# mainboard.net
KiCad netlist of a schematic drawn in EAGLE
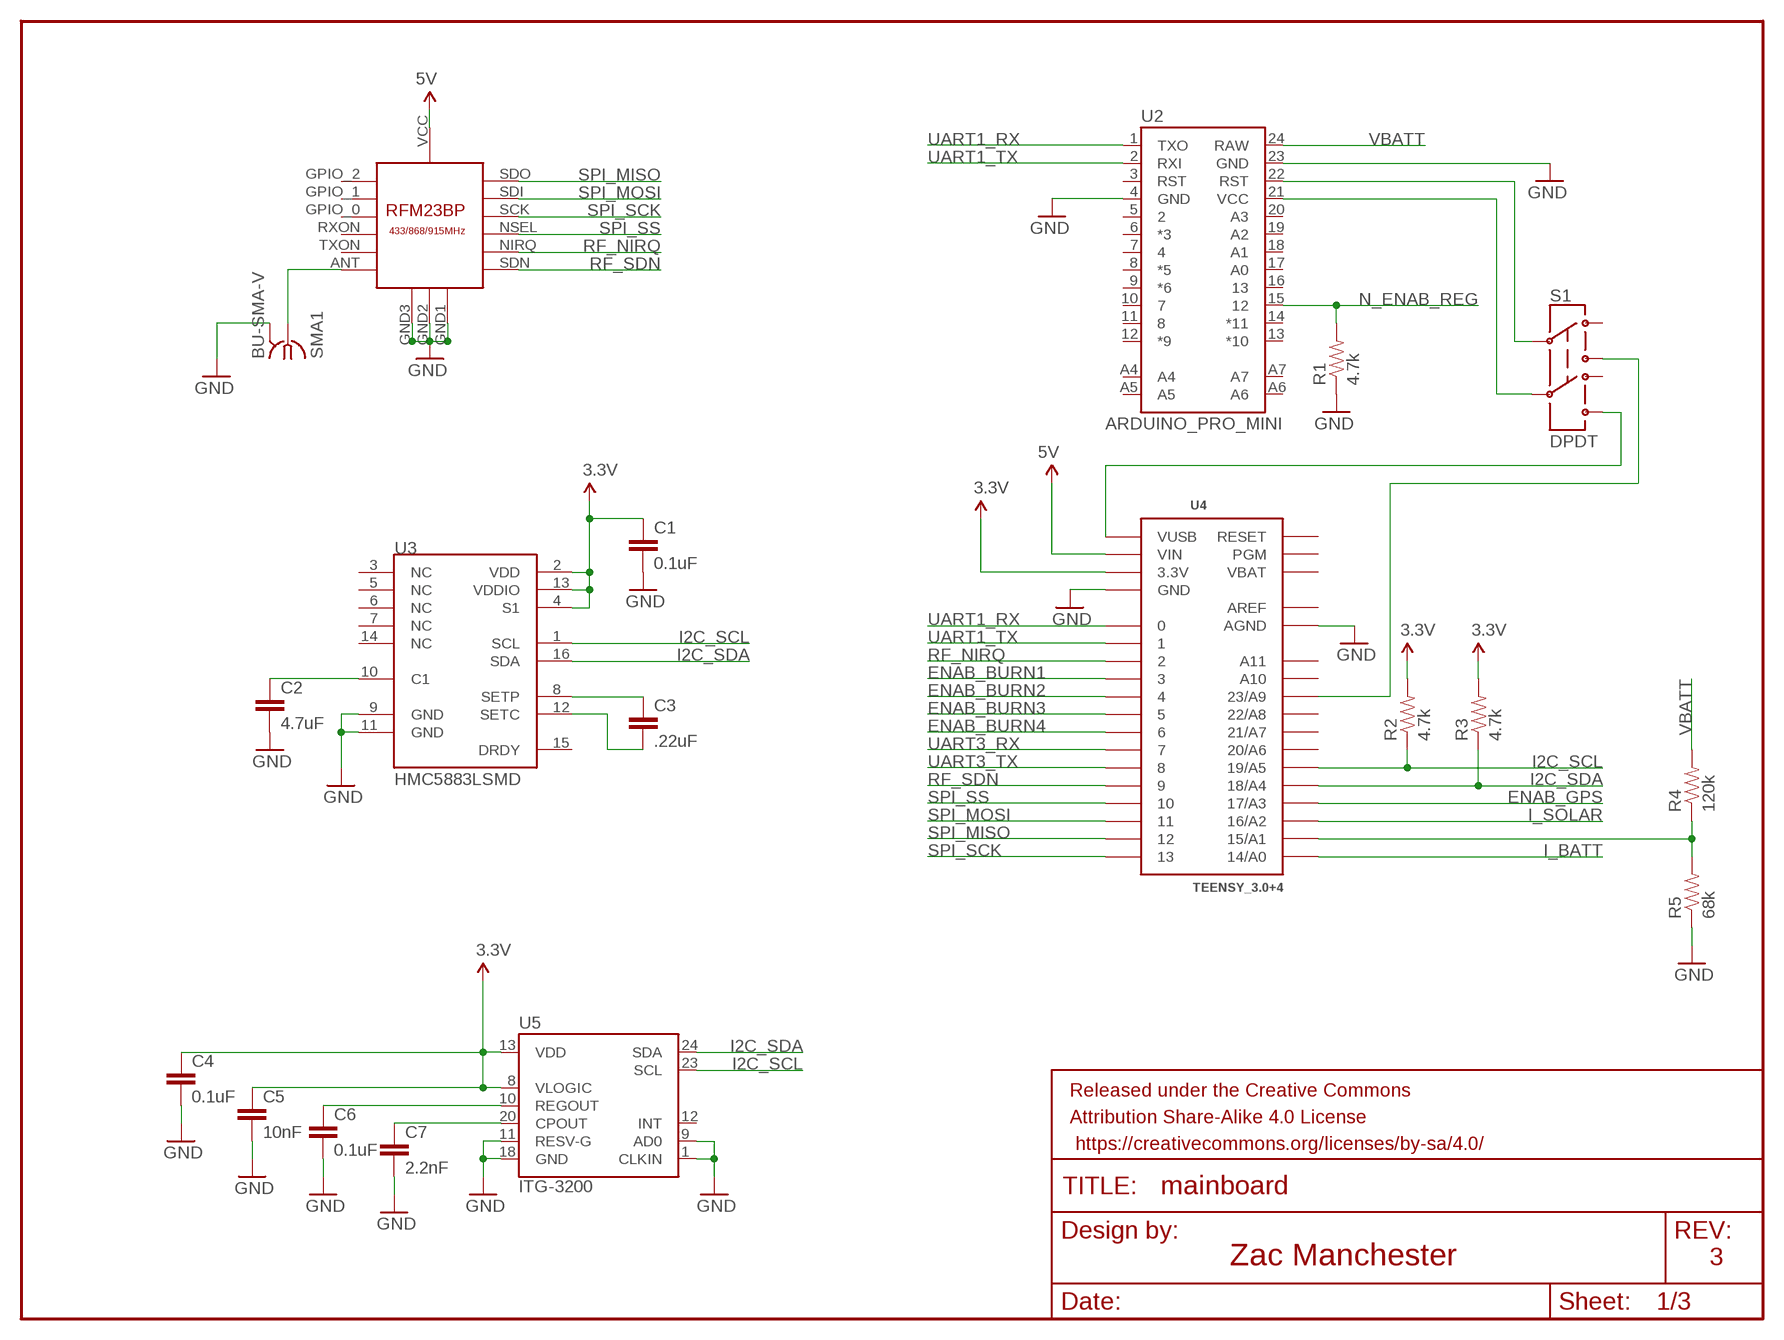
[diagram p0: schematic, sheet 1]
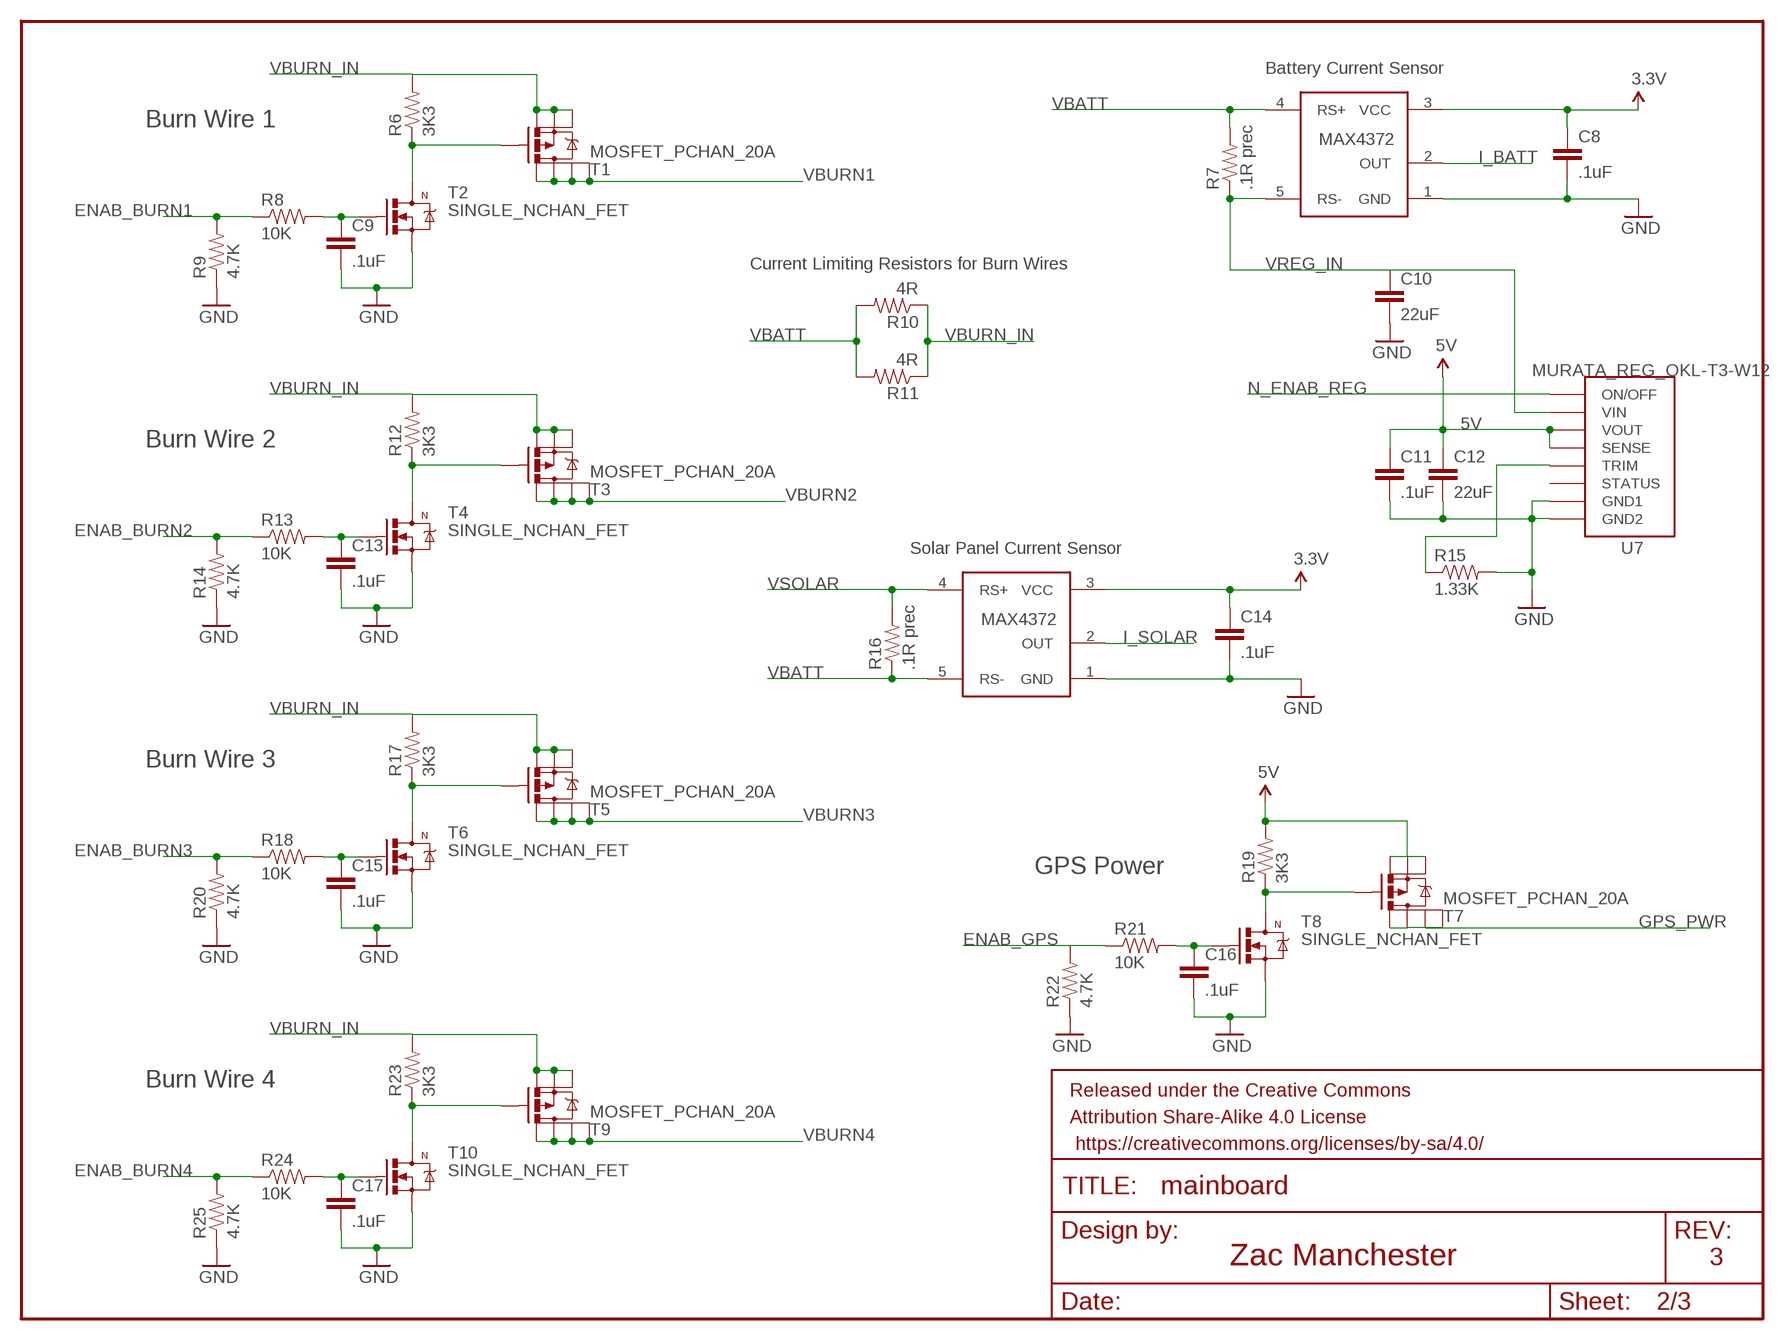
[diagram p1: schematic, sheet 2]
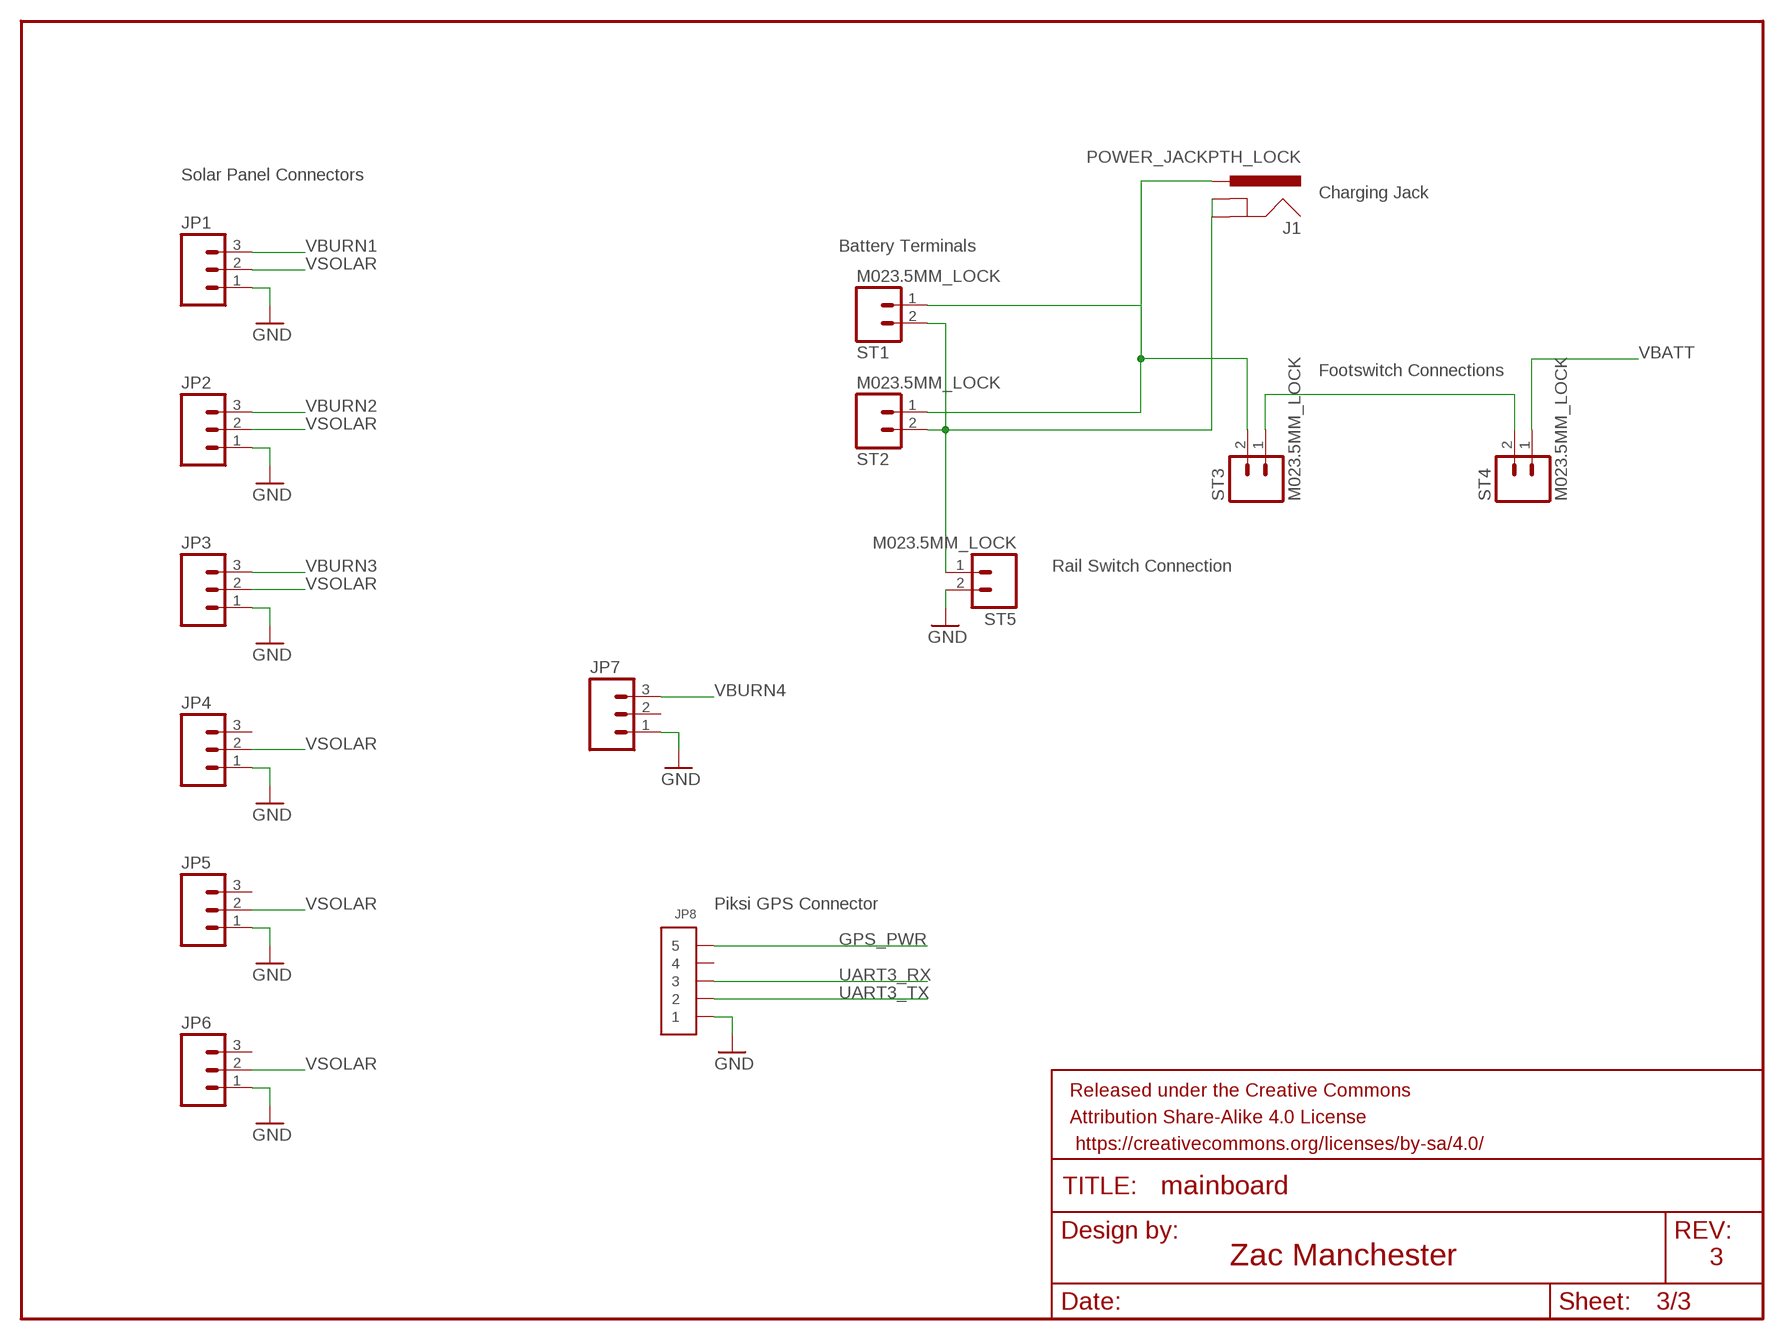
[diagram p2: schematic, sheet 3]

(export (version "E")
  (design (tool "Eeschema 10.0.6"))
  (components
    (comp (ref "FRAME3")
      (value "FRAME-LETTER")
      (footprint "eagle-import:CREATIVE_COMMONS")
      (libsource (lib "eagle-import") (part "FRAME-LETTER"))
    )
    (comp (ref "J1")
      (value "POWER_JACKPTH_LOCK")
      (footprint "eagle-import:POWER_JACK_PTH_LOCK")
      (libsource (lib "eagle-import") (part "POWER_JACKPTH_LOCK"))
    )
    (comp (ref "JP1")
      (value "M03POLAR_LOCK")
      (footprint "eagle-import:MOLEX-1X3_LOCK")
      (libsource (lib "eagle-import") (part "M03POLAR_LOCK"))
    )
    (comp (ref "JP2")
      (value "M03POLAR_LOCK")
      (footprint "eagle-import:MOLEX-1X3_LOCK")
      (libsource (lib "eagle-import") (part "M03POLAR_LOCK"))
    )
    (comp (ref "JP3")
      (value "M03POLAR_LOCK")
      (footprint "eagle-import:MOLEX-1X3_LOCK")
      (libsource (lib "eagle-import") (part "M03POLAR_LOCK"))
    )
    (comp (ref "JP4")
      (value "M03POLAR_LOCK")
      (footprint "eagle-import:MOLEX-1X3_LOCK")
      (libsource (lib "eagle-import") (part "M03POLAR_LOCK"))
    )
    (comp (ref "JP5")
      (value "M03POLAR_LOCK")
      (footprint "eagle-import:MOLEX-1X3_LOCK")
      (libsource (lib "eagle-import") (part "M03POLAR_LOCK"))
    )
    (comp (ref "JP6")
      (value "M03POLAR_LOCK")
      (footprint "eagle-import:MOLEX-1X3_LOCK")
      (libsource (lib "eagle-import") (part "M03POLAR_LOCK"))
    )
    (comp (ref "JP7")
      (value "M03POLAR_LOCK")
      (footprint "eagle-import:MOLEX-1X3_LOCK")
      (libsource (lib "eagle-import") (part "M03POLAR_LOCK"))
    )
    (comp (ref "JP8")
      (value "CONN_5-1-53261")
      (footprint "eagle-import:PB-53261-05")
      (libsource (lib "eagle-import") (part "CONN_5-1-53261"))
    )
    (comp (ref "ST1")
      (value "M023.5MM_LOCK")
      (footprint "eagle-import:SCREWTERMINAL-3.5MM-2_LOCK")
      (libsource (lib "eagle-import") (part "M023.5MM_LOCK"))
    )
    (comp (ref "ST2")
      (value "M023.5MM_LOCK")
      (footprint "eagle-import:SCREWTERMINAL-3.5MM-2_LOCK")
      (libsource (lib "eagle-import") (part "M023.5MM_LOCK"))
    )
    (comp (ref "ST3")
      (value "M023.5MM_LOCK")
      (footprint "eagle-import:SCREWTERMINAL-3.5MM-2_LOCK")
      (libsource (lib "eagle-import") (part "M023.5MM_LOCK"))
    )
    (comp (ref "ST4")
      (value "M023.5MM_LOCK")
      (footprint "eagle-import:SCREWTERMINAL-3.5MM-2_LOCK")
      (libsource (lib "eagle-import") (part "M023.5MM_LOCK"))
    )
    (comp (ref "ST5")
      (value "M023.5MM_LOCK")
      (footprint "eagle-import:SCREWTERMINAL-3.5MM-2_LOCK")
      (libsource (lib "eagle-import") (part "M023.5MM_LOCK"))
    )
    (comp (ref "C1")
      (value "0.1uF")
      (footprint "eagle-import:0805")
      (libsource (lib "eagle-import") (part "CAP0805"))
    )
    (comp (ref "C2")
      (value "4.7uF")
      (footprint "eagle-import:0805")
      (libsource (lib "eagle-import") (part "CAP0805"))
    )
    (comp (ref "C3")
      (value ".22uF")
      (footprint "eagle-import:0805")
      (libsource (lib "eagle-import") (part "CAP0805"))
    )
    (comp (ref "C4")
      (value "0.1uF")
      (footprint "eagle-import:0805")
      (libsource (lib "eagle-import") (part "CAP0805"))
    )
    (comp (ref "C5")
      (value "10nF")
      (footprint "eagle-import:0805")
      (libsource (lib "eagle-import") (part "CAP0805"))
    )
    (comp (ref "C6")
      (value "0.1uF")
      (footprint "eagle-import:0805")
      (libsource (lib "eagle-import") (part "CAP0805"))
    )
    (comp (ref "C7")
      (value "2.2nF")
      (footprint "eagle-import:0805")
      (libsource (lib "eagle-import") (part "CAP0805"))
    )
    (comp (ref "FRAME1")
      (value "FRAME-LETTER")
      (footprint "eagle-import:CREATIVE_COMMONS")
      (libsource (lib "eagle-import") (part "FRAME-LETTER"))
    )
    (comp (ref "R1")
      (value "4.7k")
      (footprint "eagle-import:0805")
      (libsource (lib "eagle-import") (part "RESISTOR0805-RES"))
    )
    (comp (ref "R2")
      (value "4.7k")
      (footprint "eagle-import:0805")
      (libsource (lib "eagle-import") (part "RESISTOR0805-RES"))
    )
    (comp (ref "R3")
      (value "4.7k")
      (footprint "eagle-import:0805")
      (libsource (lib "eagle-import") (part "RESISTOR0805-RES"))
    )
    (comp (ref "R4")
      (value "120k")
      (footprint "eagle-import:0805")
      (libsource (lib "eagle-import") (part "RESISTOR0805-RES"))
    )
    (comp (ref "R5")
      (value "68k")
      (footprint "eagle-import:0805")
      (libsource (lib "eagle-import") (part "RESISTOR0805-RES"))
    )
    (comp (ref "S1")
      (value "DPDT")
      (footprint "eagle-import:AYZ0202")
      (libsource (lib "eagle-import") (part "SWITCH-DPDTAYZ0202"))
    )
    (comp (ref "SMA1")
      (value "BU-SMA-V")
      (footprint "eagle-import:BU-SMA-V")
      (libsource (lib "eagle-import") (part "BU-SMA-V"))
    )
    (comp (ref "U1")
      (value "RFM23BP")
      (footprint "eagle-import:RFM23BP")
      (libsource (lib "eagle-import") (part "RFM23BP"))
    )
    (comp (ref "U2")
      (value "ARDUINO_PRO_MINI")
      (footprint "eagle-import:ARDUINO_PRO_MINI")
      (libsource (lib "eagle-import") (part "ARDUINO_PRO_MINI"))
    )
    (comp (ref "U3")
      (value "HMC5883LSMD")
      (footprint "eagle-import:16LPCC")
      (libsource (lib "eagle-import") (part "HMC5883LSMD"))
    )
    (comp (ref "U4")
      (value "TEENSY_3.0+4")
      (footprint "eagle-import:TEENSY_3.0+4")
      (libsource (lib "eagle-import") (part "TEENSY_3.0+4"))
    )
    (comp (ref "U5")
      (value "ITG-3200")
      (footprint "eagle-import:QFN-24")
      (libsource (lib "eagle-import") (part "ITG-3200"))
    )
    (comp (ref "C8")
      (value ".1uF")
      (footprint "eagle-import:0805")
      (libsource (lib "eagle-import") (part "CAP0805"))
    )
    (comp (ref "C9")
      (value ".1uF")
      (footprint "eagle-import:0805")
      (libsource (lib "eagle-import") (part "CAP0805"))
    )
    (comp (ref "C10")
      (value "22uF")
      (footprint "eagle-import:1206")
      (libsource (lib "eagle-import") (part "CAP1206"))
    )
    (comp (ref "C11")
      (value ".1uF")
      (footprint "eagle-import:0805")
      (libsource (lib "eagle-import") (part "CAP0805"))
    )
    (comp (ref "C12")
      (value "22uF")
      (footprint "eagle-import:1206")
      (libsource (lib "eagle-import") (part "CAP1206"))
    )
    (comp (ref "C13")
      (value ".1uF")
      (footprint "eagle-import:0805")
      (libsource (lib "eagle-import") (part "CAP0805"))
    )
    (comp (ref "C14")
      (value ".1uF")
      (footprint "eagle-import:0805")
      (libsource (lib "eagle-import") (part "CAP0805"))
    )
    (comp (ref "C15")
      (value ".1uF")
      (footprint "eagle-import:0805")
      (libsource (lib "eagle-import") (part "CAP0805"))
    )
    (comp (ref "C16")
      (value ".1uF")
      (footprint "eagle-import:0805")
      (libsource (lib "eagle-import") (part "CAP0805"))
    )
    (comp (ref "C17")
      (value ".1uF")
      (footprint "eagle-import:0805")
      (libsource (lib "eagle-import") (part "CAP0805"))
    )
    (comp (ref "FRAME2")
      (value "FRAME-LETTER")
      (footprint "eagle-import:CREATIVE_COMMONS")
      (libsource (lib "eagle-import") (part "FRAME-LETTER"))
    )
    (comp (ref "R6")
      (value "3K3")
      (footprint "eagle-import:0805")
      (libsource (lib "eagle-import") (part "RESISTOR0805-RES"))
    )
    (comp (ref "R7")
      (value ".1R prec")
      (footprint "eagle-import:0805")
      (libsource (lib "eagle-import") (part "RESISTOR0805-RES"))
    )
    (comp (ref "R8")
      (value "10K")
      (footprint "eagle-import:0805")
      (libsource (lib "eagle-import") (part "RESISTOR0805-RES"))
    )
    (comp (ref "R9")
      (value "4.7K")
      (footprint "eagle-import:0805")
      (libsource (lib "eagle-import") (part "RESISTOR0805-RES"))
    )
    (comp (ref "R10")
      (value "4R")
      (footprint "eagle-import:R2512")
      (libsource (lib "eagle-import") (part "RESISTOR2512"))
    )
    (comp (ref "R11")
      (value "4R")
      (footprint "eagle-import:R2512")
      (libsource (lib "eagle-import") (part "RESISTOR2512"))
    )
    (comp (ref "R12")
      (value "3K3")
      (footprint "eagle-import:0805")
      (libsource (lib "eagle-import") (part "RESISTOR0805-RES"))
    )
    (comp (ref "R13")
      (value "10K")
      (footprint "eagle-import:0805")
      (libsource (lib "eagle-import") (part "RESISTOR0805-RES"))
    )
    (comp (ref "R14")
      (value "4.7K")
      (footprint "eagle-import:0805")
      (libsource (lib "eagle-import") (part "RESISTOR0805-RES"))
    )
    (comp (ref "R15")
      (value "1.33K")
      (footprint "eagle-import:0805")
      (libsource (lib "eagle-import") (part "RESISTOR0805-RES"))
    )
    (comp (ref "R16")
      (value ".1R prec")
      (footprint "eagle-import:0805")
      (libsource (lib "eagle-import") (part "RESISTOR0805-RES"))
    )
    (comp (ref "R17")
      (value "3K3")
      (footprint "eagle-import:0805")
      (libsource (lib "eagle-import") (part "RESISTOR0805-RES"))
    )
    (comp (ref "R18")
      (value "10K")
      (footprint "eagle-import:0805")
      (libsource (lib "eagle-import") (part "RESISTOR0805-RES"))
    )
    (comp (ref "R19")
      (value "3K3")
      (footprint "eagle-import:0805")
      (libsource (lib "eagle-import") (part "RESISTOR0805-RES"))
    )
    (comp (ref "R20")
      (value "4.7K")
      (footprint "eagle-import:0805")
      (libsource (lib "eagle-import") (part "RESISTOR0805-RES"))
    )
    (comp (ref "R21")
      (value "10K")
      (footprint "eagle-import:0805")
      (libsource (lib "eagle-import") (part "RESISTOR0805-RES"))
    )
    (comp (ref "R22")
      (value "4.7K")
      (footprint "eagle-import:0805")
      (libsource (lib "eagle-import") (part "RESISTOR0805-RES"))
    )
    (comp (ref "R23")
      (value "3K3")
      (footprint "eagle-import:0805")
      (libsource (lib "eagle-import") (part "RESISTOR0805-RES"))
    )
    (comp (ref "R24")
      (value "10K")
      (footprint "eagle-import:0805")
      (libsource (lib "eagle-import") (part "RESISTOR0805-RES"))
    )
    (comp (ref "R25")
      (value "4.7K")
      (footprint "eagle-import:0805")
      (libsource (lib "eagle-import") (part "RESISTOR0805-RES"))
    )
    (comp (ref "T1")
      (value "MOSFET_PCHAN_20A")
      (footprint "eagle-import:SO8")
      (libsource (lib "eagle-import") (part "MOSFET_PCHAN_20A"))
    )
    (comp (ref "T2")
      (value "SINGLE_NCHAN_FET")
      (footprint "eagle-import:SOT23-3")
      (libsource (lib "eagle-import") (part "SINGLE_NCHAN_FET"))
    )
    (comp (ref "T3")
      (value "MOSFET_PCHAN_20A")
      (footprint "eagle-import:SO8")
      (libsource (lib "eagle-import") (part "MOSFET_PCHAN_20A"))
    )
    (comp (ref "T4")
      (value "SINGLE_NCHAN_FET")
      (footprint "eagle-import:SOT23-3")
      (libsource (lib "eagle-import") (part "SINGLE_NCHAN_FET"))
    )
    (comp (ref "T5")
      (value "MOSFET_PCHAN_20A")
      (footprint "eagle-import:SO8")
      (libsource (lib "eagle-import") (part "MOSFET_PCHAN_20A"))
    )
    (comp (ref "T6")
      (value "SINGLE_NCHAN_FET")
      (footprint "eagle-import:SOT23-3")
      (libsource (lib "eagle-import") (part "SINGLE_NCHAN_FET"))
    )
    (comp (ref "T7")
      (value "MOSFET_PCHAN_20A")
      (footprint "eagle-import:SO8")
      (libsource (lib "eagle-import") (part "MOSFET_PCHAN_20A"))
    )
    (comp (ref "T8")
      (value "SINGLE_NCHAN_FET")
      (footprint "eagle-import:SOT23-3")
      (libsource (lib "eagle-import") (part "SINGLE_NCHAN_FET"))
    )
    (comp (ref "T9")
      (value "MOSFET_PCHAN_20A")
      (footprint "eagle-import:SO8")
      (libsource (lib "eagle-import") (part "MOSFET_PCHAN_20A"))
    )
    (comp (ref "T10")
      (value "SINGLE_NCHAN_FET")
      (footprint "eagle-import:SOT23-3")
      (libsource (lib "eagle-import") (part "SINGLE_NCHAN_FET"))
    )
    (comp (ref "U6")
      (value "CURRENT_MAX4372")
      (footprint "eagle-import:SOT23-5")
      (libsource (lib "eagle-import") (part "CURRENT_MAX4372"))
    )
    (comp (ref "U7")
      (value "MURATA_REG_OKL-T3-W12")
      (footprint "eagle-import:MURATA_REG_OKL-T6-W12")
      (libsource (lib "eagle-import") (part "MURATA_REG_OKL-T6-W12"))
    )
    (comp (ref "U8")
      (value "CURRENT_MAX4372")
      (footprint "eagle-import:SOT23-5")
      (libsource (lib "eagle-import") (part "CURRENT_MAX4372"))
    )
  )
  (nets
    (net (code "1") (name "3.3V") (class "Default")
      (node (ref "C1") (pin "1") (pinfunction "1_1") (pintype "passive"))
      (node (ref "C14") (pin "1") (pinfunction "1_1") (pintype "passive"))
      (node (ref "C4") (pin "1") (pinfunction "1_1") (pintype "passive"))
      (node (ref "C5") (pin "1") (pinfunction "1_1") (pintype "passive"))
      (node (ref "C8") (pin "1") (pinfunction "1_1") (pintype "passive"))
      (node (ref "R2") (pin "2") (pinfunction "2_2") (pintype "passive"))
      (node (ref "R3") (pin "2") (pinfunction "2_2") (pintype "passive"))
      (node (ref "U3") (pin "13") (pinfunction "VDDIO_13") (pintype "bidirectional"))
      (node (ref "U3") (pin "2") (pinfunction "VDD_2") (pintype "bidirectional"))
      (node (ref "U3") (pin "4") (pinfunction "S1_4") (pintype "bidirectional"))
      (node (ref "U4") (pin "3.3V") (pinfunction "3.3V_3.3V") (pintype "power_in"))
      (node (ref "U4") (pin "3.3V1") (pinfunction "3.3V_3.3V1") (pintype "power_in"))
      (node (ref "U5") (pin "13") (pinfunction "VDD_13") (pintype "bidirectional"))
      (node (ref "U5") (pin "8") (pinfunction "VLOGIC_8") (pintype "bidirectional"))
      (node (ref "U6") (pin "3") (pinfunction "VCC_3") (pintype "bidirectional"))
      (node (ref "U8") (pin "3") (pinfunction "VCC_3") (pintype "bidirectional"))
    )
    (net (code "2") (name "5V") (class "Default")
      (node (ref "C11") (pin "1") (pinfunction "1_1") (pintype "passive"))
      (node (ref "C12") (pin "1") (pinfunction "1_1") (pintype "passive"))
      (node (ref "R19") (pin "2") (pinfunction "2_2") (pintype "passive"))
      (node (ref "T7") (pin "1") (pinfunction "S_1") (pintype "passive"))
      (node (ref "T7") (pin "2") (pinfunction "S_2") (pintype "passive"))
      (node (ref "T7") (pin "3") (pinfunction "S_3") (pintype "passive"))
      (node (ref "U1") (pin "VCC") (pinfunction "VCC_VCC") (pintype "power_in"))
      (node (ref "U4") (pin "VIN") (pinfunction "VIN_VIN") (pintype "power_in"))
      (node (ref "U7") (pin "4") (pinfunction "VOUT_4") (pintype "bidirectional"))
      (node (ref "U7") (pin "5") (pinfunction "SENSE_5") (pintype "bidirectional"))
    )
    (net (code "3") (name "AREF") (class "Default")
      (node (ref "U4") (pin "AREF") (pinfunction "AREF_AREF") (pintype "power_in"))
    )
    (net (code "4") (name "ENAB_BURN1") (class "Default")
      (node (ref "R8") (pin "1") (pinfunction "1_1") (pintype "passive"))
      (node (ref "R9") (pin "2") (pinfunction "2_2") (pintype "passive"))
      (node (ref "U4") (pin "3") (pinfunction "3_3") (pintype "bidirectional"))
    )
    (net (code "5") (name "ENAB_BURN2") (class "Default")
      (node (ref "R13") (pin "1") (pinfunction "1_1") (pintype "passive"))
      (node (ref "R14") (pin "2") (pinfunction "2_2") (pintype "passive"))
      (node (ref "U4") (pin "4") (pinfunction "4_4") (pintype "bidirectional"))
    )
    (net (code "6") (name "ENAB_BURN3") (class "Default")
      (node (ref "R18") (pin "1") (pinfunction "1_1") (pintype "passive"))
      (node (ref "R20") (pin "2") (pinfunction "2_2") (pintype "passive"))
      (node (ref "U4") (pin "5") (pinfunction "5_5") (pintype "bidirectional"))
    )
    (net (code "7") (name "ENAB_BURN4") (class "Default")
      (node (ref "R24") (pin "1") (pinfunction "1_1") (pintype "passive"))
      (node (ref "R25") (pin "2") (pinfunction "2_2") (pintype "passive"))
      (node (ref "U4") (pin "6") (pinfunction "6_6") (pintype "bidirectional"))
    )
    (net (code "8") (name "ENAB_GPS") (class "Default")
      (node (ref "R21") (pin "1") (pinfunction "1_1") (pintype "passive"))
      (node (ref "R22") (pin "2") (pinfunction "2_2") (pintype "passive"))
      (node (ref "U4") (pin "17/A3") (pinfunction "17/A3_17/A3") (pintype "bidirectional"))
    )
    (net (code "9") (name "GND") (class "Default")
      (node (ref "C1") (pin "2") (pinfunction "2_2") (pintype "passive"))
      (node (ref "C10") (pin "2") (pinfunction "2_2") (pintype "passive"))
      (node (ref "C11") (pin "2") (pinfunction "2_2") (pintype "passive"))
      (node (ref "C12") (pin "2") (pinfunction "2_2") (pintype "passive"))
      (node (ref "C13") (pin "2") (pinfunction "2_2") (pintype "passive"))
      (node (ref "C14") (pin "2") (pinfunction "2_2") (pintype "passive"))
      (node (ref "C15") (pin "2") (pinfunction "2_2") (pintype "passive"))
      (node (ref "C16") (pin "2") (pinfunction "2_2") (pintype "passive"))
      (node (ref "C17") (pin "2") (pinfunction "2_2") (pintype "passive"))
      (node (ref "C2") (pin "2") (pinfunction "2_2") (pintype "passive"))
      (node (ref "C4") (pin "2") (pinfunction "2_2") (pintype "passive"))
      (node (ref "C5") (pin "2") (pinfunction "2_2") (pintype "passive"))
      (node (ref "C6") (pin "2") (pinfunction "2_2") (pintype "passive"))
      (node (ref "C7") (pin "2") (pinfunction "2_2") (pintype "passive"))
      (node (ref "C8") (pin "2") (pinfunction "2_2") (pintype "passive"))
      (node (ref "C9") (pin "2") (pinfunction "2_2") (pintype "passive"))
      (node (ref "JP1") (pin "1") (pinfunction "1_1") (pintype "passive"))
      (node (ref "JP2") (pin "1") (pinfunction "1_1") (pintype "passive"))
      (node (ref "JP3") (pin "1") (pinfunction "1_1") (pintype "passive"))
      (node (ref "JP4") (pin "1") (pinfunction "1_1") (pintype "passive"))
      (node (ref "JP5") (pin "1") (pinfunction "1_1") (pintype "passive"))
      (node (ref "JP6") (pin "1") (pinfunction "1_1") (pintype "passive"))
      (node (ref "JP7") (pin "1") (pinfunction "1_1") (pintype "passive"))
      (node (ref "JP8") (pin "1") (pinfunction "1_1") (pintype "bidirectional"))
      (node (ref "R1") (pin "1") (pinfunction "1_1") (pintype "passive"))
      (node (ref "R14") (pin "1") (pinfunction "1_1") (pintype "passive"))
      (node (ref "R15") (pin "2") (pinfunction "2_2") (pintype "passive"))
      (node (ref "R20") (pin "1") (pinfunction "1_1") (pintype "passive"))
      (node (ref "R22") (pin "1") (pinfunction "1_1") (pintype "passive"))
      (node (ref "R25") (pin "1") (pinfunction "1_1") (pintype "passive"))
      (node (ref "R5") (pin "1") (pinfunction "1_1") (pintype "passive"))
      (node (ref "R9") (pin "1") (pinfunction "1_1") (pintype "passive"))
      (node (ref "SMA1") (pin "2") (pinfunction "2_2") (pintype "passive"))
      (node (ref "SMA1") (pin "3") (pinfunction "2_3") (pintype "passive"))
      (node (ref "SMA1") (pin "4") (pinfunction "2_4") (pintype "passive"))
      (node (ref "SMA1") (pin "5") (pinfunction "2_5") (pintype "passive"))
      (node (ref "ST5") (pin "2") (pinfunction "2_2") (pintype "passive"))
      (node (ref "T10") (pin "2") (pinfunction "S_2") (pintype "passive"))
      (node (ref "T2") (pin "2") (pinfunction "S_2") (pintype "passive"))
      (node (ref "T4") (pin "2") (pinfunction "S_2") (pintype "passive"))
      (node (ref "T6") (pin "2") (pinfunction "S_2") (pintype "passive"))
      (node (ref "T8") (pin "2") (pinfunction "S_2") (pintype "passive"))
      (node (ref "U1") (pin "GND1") (pinfunction "GND1_GND1") (pintype "power_in"))
      (node (ref "U1") (pin "GND2") (pinfunction "GND2_GND2") (pintype "power_in"))
      (node (ref "U1") (pin "GND3") (pinfunction "GND3_GND3") (pintype "power_in"))
      (node (ref "U2") (pin "23") (pinfunction "GND_23") (pintype "bidirectional"))
      (node (ref "U2") (pin "4") (pinfunction "GND_4") (pintype "bidirectional"))
      (node (ref "U3") (pin "11") (pinfunction "GND_11") (pintype "bidirectional"))
      (node (ref "U3") (pin "9") (pinfunction "GND_9") (pintype "bidirectional"))
      (node (ref "U4") (pin "AGND") (pinfunction "AGND_AGND") (pintype "power_in"))
      (node (ref "U4") (pin "GND") (pinfunction "GND_GND") (pintype "power_in"))
      (node (ref "U4") (pin "GND1") (pinfunction "GND_GND1") (pintype "power_in"))
      (node (ref "U5") (pin "1") (pinfunction "CLKIN_1") (pintype "bidirectional"))
      (node (ref "U5") (pin "11") (pinfunction "RESV-G_11") (pintype "bidirectional"))
      (node (ref "U5") (pin "18") (pinfunction "GND_18") (pintype "bidirectional"))
      (node (ref "U5") (pin "9") (pinfunction "AD0_9") (pintype "bidirectional"))
      (node (ref "U6") (pin "1") (pinfunction "GND_1") (pintype "bidirectional"))
      (node (ref "U7") (pin "3") (pinfunction "GND1_3") (pintype "bidirectional"))
      (node (ref "U7") (pin "7") (pinfunction "GND2_7") (pintype "bidirectional"))
      (node (ref "U8") (pin "1") (pinfunction "GND_1") (pintype "bidirectional"))
    )
    (net (code "10") (name "GPS_PWR") (class "Default")
      (node (ref "JP8") (pin "5") (pinfunction "5_5") (pintype "bidirectional"))
      (node (ref "T7") (pin "5") (pinfunction "D_5") (pintype "passive"))
      (node (ref "T7") (pin "6") (pinfunction "D_6") (pintype "passive"))
      (node (ref "T7") (pin "7") (pinfunction "D_7") (pintype "passive"))
      (node (ref "T7") (pin "8") (pinfunction "D_8") (pintype "passive"))
    )
    (net (code "11") (name "I2C_SCL") (class "Default")
      (node (ref "R2") (pin "1") (pinfunction "1_1") (pintype "passive"))
      (node (ref "U3") (pin "1") (pinfunction "SCL_1") (pintype "bidirectional"))
      (node (ref "U4") (pin "19/A5") (pinfunction "19/A5_19/A5") (pintype "bidirectional"))
      (node (ref "U5") (pin "23") (pinfunction "SCL_23") (pintype "bidirectional"))
    )
    (net (code "12") (name "I2C_SDA") (class "Default")
      (node (ref "R3") (pin "1") (pinfunction "1_1") (pintype "passive"))
      (node (ref "U3") (pin "16") (pinfunction "SDA_16") (pintype "bidirectional"))
      (node (ref "U4") (pin "18/A4") (pinfunction "18/A4_18/A4") (pintype "bidirectional"))
      (node (ref "U5") (pin "24") (pinfunction "SDA_24") (pintype "bidirectional"))
    )
    (net (code "13") (name "I_BATT") (class "Default")
      (node (ref "U4") (pin "14/A0") (pinfunction "14/A0_14/A0") (pintype "bidirectional"))
      (node (ref "U6") (pin "2") (pinfunction "OUT_2") (pintype "bidirectional"))
    )
    (net (code "14") (name "I_SOLAR") (class "Default")
      (node (ref "U4") (pin "16/A2") (pinfunction "16/A2_16/A2") (pintype "bidirectional"))
      (node (ref "U8") (pin "2") (pinfunction "OUT_2") (pintype "bidirectional"))
    )
    (net (code "15") (name "N_ENAB_REG") (class "Default")
      (node (ref "R1") (pin "2") (pinfunction "2_2") (pintype "passive"))
      (node (ref "U2") (pin "15") (pinfunction "12_15") (pintype "bidirectional"))
      (node (ref "U7") (pin "1") (pinfunction "ON/OFF_1") (pintype "bidirectional"))
    )
    (net (code "16") (name "Net-(J1-PadGND)") (class "Default")
      (node (ref "J1") (pin "GND") (pinfunction "GND_GND") (pintype "bidirectional"))
      (node (ref "J1") (pin "GNDBREAK") (pinfunction "GNDBREAK_GNDBREAK") (pintype "bidirectional"))
      (node (ref "ST1") (pin "2") (pinfunction "2_2") (pintype "passive"))
      (node (ref "ST2") (pin "2") (pinfunction "2_2") (pintype "passive"))
      (node (ref "ST5") (pin "1") (pinfunction "1_1") (pintype "passive"))
    )
    (net (code "17") (name "Net-(J1-PadPWR)") (class "Default")
      (node (ref "J1") (pin "PWR") (pinfunction "PWR_PWR") (pintype "bidirectional"))
      (node (ref "ST1") (pin "1") (pinfunction "1_1") (pintype "passive"))
      (node (ref "ST2") (pin "1") (pinfunction "1_1") (pintype "passive"))
      (node (ref "ST3") (pin "2") (pinfunction "2_2") (pintype "passive"))
    )
    (net (code "18") (name "Net-(R4-Pad1)") (class "Default")
      (node (ref "R4") (pin "1") (pinfunction "1_1") (pintype "passive"))
      (node (ref "R5") (pin "2") (pinfunction "2_2") (pintype "passive"))
      (node (ref "U4") (pin "15/A1") (pinfunction "15/A1_15/A1") (pintype "bidirectional"))
    )
    (net (code "19") (name "Net-(S1-Pad2)") (class "Default")
      (node (ref "S1") (pin "2") (pinfunction "2_2") (pintype "bidirectional"))
      (node (ref "U2") (pin "22") (pinfunction "RST_22") (pintype "bidirectional"))
    )
    (net (code "20") (name "Net-(S1-Pad3)") (class "Default")
      (node (ref "S1") (pin "3") (pinfunction "3_3") (pintype "bidirectional"))
      (node (ref "U4") (pin "23/A9") (pinfunction "23/A9_23/A9") (pintype "bidirectional"))
    )
    (net (code "21") (name "Net-(S1-Pad6)") (class "Default")
      (node (ref "S1") (pin "6") (pinfunction "6_6") (pintype "bidirectional"))
      (node (ref "U4") (pin "VUSB") (pinfunction "VUSB_VUSB") (pintype "power_in"))
    )
    (net (code "22") (name "Net-(SMA1-Pad1)") (class "Default")
      (node (ref "SMA1") (pin "1") (pinfunction "1_1") (pintype "passive"))
      (node (ref "U1") (pin "ANT") (pinfunction "ANT_ANT") (pintype "bidirectional"))
    )
    (net (code "23") (name "Net-(ST3-Pad1)") (class "Default")
      (node (ref "ST3") (pin "1") (pinfunction "1_1") (pintype "passive"))
      (node (ref "ST4") (pin "2") (pinfunction "2_2") (pintype "passive"))
    )
    (net (code "24") (name "Net-(T1-G)") (class "Default")
      (node (ref "R6") (pin "1") (pinfunction "1_1") (pintype "passive"))
      (node (ref "T1") (pin "4") (pinfunction "G_4") (pintype "passive"))
      (node (ref "T2") (pin "3") (pinfunction "D_3") (pintype "passive"))
    )
    (net (code "25") (name "Net-(T2-G)") (class "Default")
      (node (ref "C9") (pin "1") (pinfunction "1_1") (pintype "passive"))
      (node (ref "R8") (pin "2") (pinfunction "2_2") (pintype "passive"))
      (node (ref "T2") (pin "1") (pinfunction "G_1") (pintype "passive"))
    )
    (net (code "26") (name "Net-(T3-G)") (class "Default")
      (node (ref "R12") (pin "1") (pinfunction "1_1") (pintype "passive"))
      (node (ref "T3") (pin "4") (pinfunction "G_4") (pintype "passive"))
      (node (ref "T4") (pin "3") (pinfunction "D_3") (pintype "passive"))
    )
    (net (code "27") (name "Net-(T4-G)") (class "Default")
      (node (ref "C13") (pin "1") (pinfunction "1_1") (pintype "passive"))
      (node (ref "R13") (pin "2") (pinfunction "2_2") (pintype "passive"))
      (node (ref "T4") (pin "1") (pinfunction "G_1") (pintype "passive"))
    )
    (net (code "28") (name "Net-(T5-G)") (class "Default")
      (node (ref "R17") (pin "1") (pinfunction "1_1") (pintype "passive"))
      (node (ref "T5") (pin "4") (pinfunction "G_4") (pintype "passive"))
      (node (ref "T6") (pin "3") (pinfunction "D_3") (pintype "passive"))
    )
    (net (code "29") (name "Net-(T6-G)") (class "Default")
      (node (ref "C15") (pin "1") (pinfunction "1_1") (pintype "passive"))
      (node (ref "R18") (pin "2") (pinfunction "2_2") (pintype "passive"))
      (node (ref "T6") (pin "1") (pinfunction "G_1") (pintype "passive"))
    )
    (net (code "30") (name "Net-(T7-G)") (class "Default")
      (node (ref "R19") (pin "1") (pinfunction "1_1") (pintype "passive"))
      (node (ref "T7") (pin "4") (pinfunction "G_4") (pintype "passive"))
      (node (ref "T8") (pin "3") (pinfunction "D_3") (pintype "passive"))
    )
    (net (code "31") (name "Net-(T8-G)") (class "Default")
      (node (ref "C16") (pin "1") (pinfunction "1_1") (pintype "passive"))
      (node (ref "R21") (pin "2") (pinfunction "2_2") (pintype "passive"))
      (node (ref "T8") (pin "1") (pinfunction "G_1") (pintype "passive"))
    )
    (net (code "32") (name "Net-(T10-D)") (class "Default")
      (node (ref "R23") (pin "1") (pinfunction "1_1") (pintype "passive"))
      (node (ref "T10") (pin "3") (pinfunction "D_3") (pintype "passive"))
      (node (ref "T9") (pin "4") (pinfunction "G_4") (pintype "passive"))
    )
    (net (code "33") (name "Net-(T10-G)") (class "Default")
      (node (ref "C17") (pin "1") (pinfunction "1_1") (pintype "passive"))
      (node (ref "R24") (pin "2") (pinfunction "2_2") (pintype "passive"))
      (node (ref "T10") (pin "1") (pinfunction "G_1") (pintype "passive"))
    )
    (net (code "34") (name "Net-(U2-VCC)") (class "Default")
      (node (ref "S1") (pin "5") (pinfunction "5_5") (pintype "bidirectional"))
      (node (ref "U2") (pin "21") (pinfunction "VCC_21") (pintype "bidirectional"))
    )
    (net (code "35") (name "Net-(U3-C1)") (class "Default")
      (node (ref "C2") (pin "1") (pinfunction "1_1") (pintype "passive"))
      (node (ref "U3") (pin "10") (pinfunction "C1_10") (pintype "bidirectional"))
    )
    (net (code "36") (name "Net-(U3-SETC)") (class "Default")
      (node (ref "C3") (pin "2") (pinfunction "2_2") (pintype "passive"))
      (node (ref "U3") (pin "12") (pinfunction "SETC_12") (pintype "bidirectional"))
    )
    (net (code "37") (name "Net-(U3-SETP)") (class "Default")
      (node (ref "C3") (pin "1") (pinfunction "1_1") (pintype "passive"))
      (node (ref "U3") (pin "8") (pinfunction "SETP_8") (pintype "bidirectional"))
    )
    (net (code "38") (name "Net-(U5-CPOUT)") (class "Default")
      (node (ref "C7") (pin "1") (pinfunction "1_1") (pintype "passive"))
      (node (ref "U5") (pin "20") (pinfunction "CPOUT_20") (pintype "bidirectional"))
    )
    (net (code "39") (name "Net-(U5-REGOUT)") (class "Default")
      (node (ref "C6") (pin "1") (pinfunction "1_1") (pintype "passive"))
      (node (ref "U5") (pin "10") (pinfunction "REGOUT_10") (pintype "bidirectional"))
    )
    (net (code "40") (name "Net-(U7-TRIM)") (class "Default")
      (node (ref "R15") (pin "1") (pinfunction "1_1") (pintype "passive"))
      (node (ref "U7") (pin "6") (pinfunction "TRIM_6") (pintype "bidirectional"))
    )
    (net (code "41") (name "RF_NIRQ") (class "Default")
      (node (ref "U1") (pin "NIRQ") (pinfunction "NIRQ_NIRQ") (pintype "bidirectional"))
      (node (ref "U4") (pin "2") (pinfunction "2_2") (pintype "bidirectional"))
    )
    (net (code "42") (name "RF_SDN") (class "Default")
      (node (ref "U1") (pin "SDN") (pinfunction "SDN_SDN") (pintype "bidirectional"))
      (node (ref "U4") (pin "9") (pinfunction "9_9") (pintype "bidirectional"))
    )
    (net (code "43") (name "SPI_MISO") (class "Default")
      (node (ref "U1") (pin "SDO") (pinfunction "SDO_SDO") (pintype "bidirectional"))
      (node (ref "U4") (pin "12") (pinfunction "12_12") (pintype "bidirectional"))
    )
    (net (code "44") (name "SPI_MOSI") (class "Default")
      (node (ref "U1") (pin "SDI") (pinfunction "SDI_SDI") (pintype "bidirectional"))
      (node (ref "U4") (pin "11") (pinfunction "11_11") (pintype "bidirectional"))
    )
    (net (code "45") (name "SPI_SCK") (class "Default")
      (node (ref "U1") (pin "SCK") (pinfunction "SCK_SCK") (pintype "bidirectional"))
      (node (ref "U4") (pin "13") (pinfunction "13_13") (pintype "bidirectional"))
    )
    (net (code "46") (name "SPI_SS") (class "Default")
      (node (ref "U1") (pin "NSEL") (pinfunction "NSEL_NSEL") (pintype "bidirectional"))
      (node (ref "U4") (pin "10") (pinfunction "10_10") (pintype "bidirectional"))
    )
    (net (code "47") (name "UART1_RX") (class "Default")
      (node (ref "U2") (pin "1") (pinfunction "TXO_1") (pintype "bidirectional"))
      (node (ref "U4") (pin "0") (pinfunction "0_0") (pintype "bidirectional"))
    )
    (net (code "48") (name "UART1_TX") (class "Default")
      (node (ref "U2") (pin "2") (pinfunction "RXI_2") (pintype "bidirectional"))
      (node (ref "U4") (pin "1") (pinfunction "1_1") (pintype "bidirectional"))
    )
    (net (code "49") (name "UART3_RX") (class "Default")
      (node (ref "JP8") (pin "3") (pinfunction "3_3") (pintype "bidirectional"))
      (node (ref "U4") (pin "7") (pinfunction "7_7") (pintype "bidirectional"))
    )
    (net (code "50") (name "UART3_TX") (class "Default")
      (node (ref "JP8") (pin "2") (pinfunction "2_2") (pintype "bidirectional"))
      (node (ref "U4") (pin "8") (pinfunction "8_8") (pintype "bidirectional"))
    )
    (net (code "51") (name "VBAT") (class "Default")
      (node (ref "U4") (pin "VBAT") (pinfunction "VBAT_VBAT") (pintype "power_in"))
    )
    (net (code "52") (name "VBATT") (class "Default")
      (node (ref "R10") (pin "2") (pinfunction "2_2") (pintype "passive"))
      (node (ref "R11") (pin "2") (pinfunction "2_2") (pintype "passive"))
      (node (ref "R16") (pin "1") (pinfunction "1_1") (pintype "passive"))
      (node (ref "R4") (pin "2") (pinfunction "2_2") (pintype "passive"))
      (node (ref "R7") (pin "2") (pinfunction "2_2") (pintype "passive"))
      (node (ref "ST4") (pin "1") (pinfunction "1_1") (pintype "passive"))
      (node (ref "U2") (pin "24") (pinfunction "RAW_24") (pintype "bidirectional"))
      (node (ref "U6") (pin "4") (pinfunction "RS+_4") (pintype "bidirectional"))
      (node (ref "U8") (pin "5") (pinfunction "RS-_5") (pintype "bidirectional"))
    )
    (net (code "53") (name "VBURN1") (class "Default")
      (node (ref "JP1") (pin "3") (pinfunction "3_3") (pintype "passive"))
      (node (ref "T1") (pin "5") (pinfunction "D_5") (pintype "passive"))
      (node (ref "T1") (pin "6") (pinfunction "D_6") (pintype "passive"))
      (node (ref "T1") (pin "7") (pinfunction "D_7") (pintype "passive"))
      (node (ref "T1") (pin "8") (pinfunction "D_8") (pintype "passive"))
    )
    (net (code "54") (name "VBURN2") (class "Default")
      (node (ref "JP2") (pin "3") (pinfunction "3_3") (pintype "passive"))
      (node (ref "T3") (pin "5") (pinfunction "D_5") (pintype "passive"))
      (node (ref "T3") (pin "6") (pinfunction "D_6") (pintype "passive"))
      (node (ref "T3") (pin "7") (pinfunction "D_7") (pintype "passive"))
      (node (ref "T3") (pin "8") (pinfunction "D_8") (pintype "passive"))
    )
    (net (code "55") (name "VBURN3") (class "Default")
      (node (ref "JP3") (pin "3") (pinfunction "3_3") (pintype "passive"))
      (node (ref "T5") (pin "5") (pinfunction "D_5") (pintype "passive"))
      (node (ref "T5") (pin "6") (pinfunction "D_6") (pintype "passive"))
      (node (ref "T5") (pin "7") (pinfunction "D_7") (pintype "passive"))
      (node (ref "T5") (pin "8") (pinfunction "D_8") (pintype "passive"))
    )
    (net (code "56") (name "VBURN4") (class "Default")
      (node (ref "JP7") (pin "3") (pinfunction "3_3") (pintype "passive"))
      (node (ref "T9") (pin "5") (pinfunction "D_5") (pintype "passive"))
      (node (ref "T9") (pin "6") (pinfunction "D_6") (pintype "passive"))
      (node (ref "T9") (pin "7") (pinfunction "D_7") (pintype "passive"))
      (node (ref "T9") (pin "8") (pinfunction "D_8") (pintype "passive"))
    )
    (net (code "57") (name "VBURN_IN") (class "Default")
      (node (ref "R10") (pin "1") (pinfunction "1_1") (pintype "passive"))
      (node (ref "R11") (pin "1") (pinfunction "1_1") (pintype "passive"))
      (node (ref "R12") (pin "2") (pinfunction "2_2") (pintype "passive"))
      (node (ref "R17") (pin "2") (pinfunction "2_2") (pintype "passive"))
      (node (ref "R23") (pin "2") (pinfunction "2_2") (pintype "passive"))
      (node (ref "R6") (pin "2") (pinfunction "2_2") (pintype "passive"))
      (node (ref "T1") (pin "1") (pinfunction "S_1") (pintype "passive"))
      (node (ref "T1") (pin "2") (pinfunction "S_2") (pintype "passive"))
      (node (ref "T1") (pin "3") (pinfunction "S_3") (pintype "passive"))
      (node (ref "T3") (pin "1") (pinfunction "S_1") (pintype "passive"))
      (node (ref "T3") (pin "2") (pinfunction "S_2") (pintype "passive"))
      (node (ref "T3") (pin "3") (pinfunction "S_3") (pintype "passive"))
      (node (ref "T5") (pin "1") (pinfunction "S_1") (pintype "passive"))
      (node (ref "T5") (pin "2") (pinfunction "S_2") (pintype "passive"))
      (node (ref "T5") (pin "3") (pinfunction "S_3") (pintype "passive"))
      (node (ref "T9") (pin "1") (pinfunction "S_1") (pintype "passive"))
      (node (ref "T9") (pin "2") (pinfunction "S_2") (pintype "passive"))
      (node (ref "T9") (pin "3") (pinfunction "S_3") (pintype "passive"))
    )
    (net (code "58") (name "VREG_IN") (class "Default")
      (node (ref "C10") (pin "1") (pinfunction "1_1") (pintype "passive"))
      (node (ref "R7") (pin "1") (pinfunction "1_1") (pintype "passive"))
      (node (ref "U6") (pin "5") (pinfunction "RS-_5") (pintype "bidirectional"))
      (node (ref "U7") (pin "2") (pinfunction "VIN_2") (pintype "bidirectional"))
    )
    (net (code "59") (name "VSOLAR") (class "Default")
      (node (ref "JP1") (pin "2") (pinfunction "2_2") (pintype "passive"))
      (node (ref "JP2") (pin "2") (pinfunction "2_2") (pintype "passive"))
      (node (ref "JP3") (pin "2") (pinfunction "2_2") (pintype "passive"))
      (node (ref "JP4") (pin "2") (pinfunction "2_2") (pintype "passive"))
      (node (ref "JP5") (pin "2") (pinfunction "2_2") (pintype "passive"))
      (node (ref "JP6") (pin "2") (pinfunction "2_2") (pintype "passive"))
      (node (ref "R16") (pin "2") (pinfunction "2_2") (pintype "passive"))
      (node (ref "U8") (pin "4") (pinfunction "RS+_4") (pintype "bidirectional"))
    )
    (net (code "60") (name "unconnected-(JP4-Pad3)") (class "Default")
      (node (ref "JP4") (pin "3") (pinfunction "3_3") (pintype "passive"))
    )
    (net (code "61") (name "unconnected-(JP5-Pad3)") (class "Default")
      (node (ref "JP5") (pin "3") (pinfunction "3_3") (pintype "passive"))
    )
    (net (code "62") (name "unconnected-(JP6-Pad3)") (class "Default")
      (node (ref "JP6") (pin "3") (pinfunction "3_3") (pintype "passive"))
    )
    (net (code "63") (name "unconnected-(JP7-Pad2)") (class "Default")
      (node (ref "JP7") (pin "2") (pinfunction "2_2") (pintype "passive"))
    )
    (net (code "64") (name "unconnected-(JP8-Pad4)") (class "Default")
      (node (ref "JP8") (pin "4") (pinfunction "4_4") (pintype "bidirectional"))
    )
    (net (code "65") (name "unconnected-(S1-Pad1)") (class "Default")
      (node (ref "S1") (pin "1") (pinfunction "1_1") (pintype "bidirectional"))
    )
    (net (code "66") (name "unconnected-(S1-Pad4)") (class "Default")
      (node (ref "S1") (pin "4") (pinfunction "4_4") (pintype "bidirectional"))
    )
    (net (code "67") (name "unconnected-(U1-PadGPIO_0)") (class "Default")
      (node (ref "U1") (pin "GPIO_0") (pinfunction "GPIO_0_GPIO_0") (pintype "bidirectional"))
    )
    (net (code "68") (name "unconnected-(U1-PadGPIO_1)") (class "Default")
      (node (ref "U1") (pin "GPIO_1") (pinfunction "GPIO_1_GPIO_1") (pintype "bidirectional"))
    )
    (net (code "69") (name "unconnected-(U1-PadGPIO_2)") (class "Default")
      (node (ref "U1") (pin "GPIO_2") (pinfunction "GPIO_2_GPIO_2") (pintype "bidirectional"))
    )
    (net (code "70") (name "unconnected-(U1-PadRXON)") (class "Default")
      (node (ref "U1") (pin "RXON") (pinfunction "RXON_RXON") (pintype "bidirectional"))
    )
    (net (code "71") (name "unconnected-(U1-PadTXON)") (class "Default")
      (node (ref "U1") (pin "TXON") (pinfunction "TXON_TXON") (pintype "bidirectional"))
    )
    (net (code "72") (name "unconnected-(U2-*3-Pad6)") (class "Default")
      (node (ref "U2") (pin "6") (pinfunction "*3_6") (pintype "bidirectional"))
    )
    (net (code "73") (name "unconnected-(U2-*5-Pad8)") (class "Default")
      (node (ref "U2") (pin "8") (pinfunction "*5_8") (pintype "bidirectional"))
    )
    (net (code "74") (name "unconnected-(U2-*6-Pad9)") (class "Default")
      (node (ref "U2") (pin "9") (pinfunction "*6_9") (pintype "bidirectional"))
    )
    (net (code "75") (name "unconnected-(U2-*9-Pad12)") (class "Default")
      (node (ref "U2") (pin "12") (pinfunction "*9_12") (pintype "bidirectional"))
    )
    (net (code "76") (name "unconnected-(U2-*10-Pad13)") (class "Default")
      (node (ref "U2") (pin "13") (pinfunction "*10_13") (pintype "bidirectional"))
    )
    (net (code "77") (name "unconnected-(U2-*11-Pad14)") (class "Default")
      (node (ref "U2") (pin "14") (pinfunction "*11_14") (pintype "bidirectional"))
    )
    (net (code "78") (name "unconnected-(U2-2-Pad5)") (class "Default")
      (node (ref "U2") (pin "5") (pinfunction "2_5") (pintype "bidirectional"))
    )
    (net (code "79") (name "unconnected-(U2-4-Pad7)") (class "Default")
      (node (ref "U2") (pin "7") (pinfunction "4_7") (pintype "bidirectional"))
    )
    (net (code "80") (name "unconnected-(U2-7-Pad10)") (class "Default")
      (node (ref "U2") (pin "10") (pinfunction "7_10") (pintype "bidirectional"))
    )
    (net (code "81") (name "unconnected-(U2-8-Pad11)") (class "Default")
      (node (ref "U2") (pin "11") (pinfunction "8_11") (pintype "bidirectional"))
    )
    (net (code "82") (name "unconnected-(U2-13-Pad16)") (class "Default")
      (node (ref "U2") (pin "16") (pinfunction "13_16") (pintype "bidirectional"))
    )
    (net (code "83") (name "unconnected-(U2-A0-Pad17)") (class "Default")
      (node (ref "U2") (pin "17") (pinfunction "A0_17") (pintype "bidirectional"))
    )
    (net (code "84") (name "unconnected-(U2-A1-Pad18)") (class "Default")
      (node (ref "U2") (pin "18") (pinfunction "A1_18") (pintype "bidirectional"))
    )
    (net (code "85") (name "unconnected-(U2-A2-Pad19)") (class "Default")
      (node (ref "U2") (pin "19") (pinfunction "A2_19") (pintype "bidirectional"))
    )
    (net (code "86") (name "unconnected-(U2-A3-Pad20)") (class "Default")
      (node (ref "U2") (pin "20") (pinfunction "A3_20") (pintype "bidirectional"))
    )
    (net (code "87") (name "unconnected-(U2-PadA4)") (class "Default")
      (node (ref "U2") (pin "A4") (pinfunction "A4_A4") (pintype "bidirectional"))
    )
    (net (code "88") (name "unconnected-(U2-PadA5)") (class "Default")
      (node (ref "U2") (pin "A5") (pinfunction "A5_A5") (pintype "bidirectional"))
    )
    (net (code "89") (name "unconnected-(U2-PadA6)") (class "Default")
      (node (ref "U2") (pin "A6") (pinfunction "A6_A6") (pintype "bidirectional"))
    )
    (net (code "90") (name "unconnected-(U2-PadA7)") (class "Default")
      (node (ref "U2") (pin "A7") (pinfunction "A7_A7") (pintype "bidirectional"))
    )
    (net (code "91") (name "unconnected-(U2-RST-Pad3)") (class "Default")
      (node (ref "U2") (pin "3") (pinfunction "RST_3") (pintype "bidirectional"))
    )
    (net (code "92") (name "unconnected-(U3-DRDY-Pad15)") (class "Default")
      (node (ref "U3") (pin "15") (pinfunction "DRDY_15") (pintype "bidirectional"))
    )
    (net (code "93") (name "unconnected-(U3-NC-Pad3)") (class "Default")
      (node (ref "U3") (pin "3") (pinfunction "NC_3") (pintype "bidirectional"))
    )
    (net (code "94") (name "unconnected-(U3-NC-Pad5)") (class "Default")
      (node (ref "U3") (pin "5") (pinfunction "NC_5") (pintype "bidirectional"))
    )
    (net (code "95") (name "unconnected-(U3-NC-Pad6)") (class "Default")
      (node (ref "U3") (pin "6") (pinfunction "NC_6") (pintype "bidirectional"))
    )
    (net (code "96") (name "unconnected-(U3-NC-Pad7)") (class "Default")
      (node (ref "U3") (pin "7") (pinfunction "NC_7") (pintype "bidirectional"))
    )
    (net (code "97") (name "unconnected-(U3-NC-Pad14)") (class "Default")
      (node (ref "U3") (pin "14") (pinfunction "NC_14") (pintype "bidirectional"))
    )
    (net (code "98") (name "unconnected-(U4-Pad20{slash}A6)") (class "Default")
      (node (ref "U4") (pin "20/A6") (pinfunction "20/A6_20/A6") (pintype "bidirectional"))
    )
    (net (code "99") (name "unconnected-(U4-Pad21{slash}A7)") (class "Default")
      (node (ref "U4") (pin "21/A7") (pinfunction "21/A7_21/A7") (pintype "bidirectional"))
    )
    (net (code "100") (name "unconnected-(U4-Pad22{slash}A8)") (class "Default")
      (node (ref "U4") (pin "22/A8") (pinfunction "22/A8_22/A8") (pintype "bidirectional"))
    )
    (net (code "101") (name "unconnected-(U4-PadA10)") (class "Default")
      (node (ref "U4") (pin "A10") (pinfunction "A10_A10") (pintype "bidirectional"))
    )
    (net (code "102") (name "unconnected-(U4-PadA11)") (class "Default")
      (node (ref "U4") (pin "A11") (pinfunction "A11_A11") (pintype "bidirectional"))
    )
    (net (code "103") (name "unconnected-(U4-PadPGM)") (class "Default")
      (node (ref "U4") (pin "PGM") (pinfunction "PGM_PGM") (pintype "bidirectional"))
    )
    (net (code "104") (name "unconnected-(U4-PadRESET)") (class "Default")
      (node (ref "U4") (pin "RESET") (pinfunction "RESET_RESET") (pintype "bidirectional"))
    )
    (net (code "105") (name "unconnected-(U5-INT-Pad12)") (class "Default")
      (node (ref "U5") (pin "12") (pinfunction "INT_12") (pintype "bidirectional"))
    )
    (net (code "106") (name "unconnected-(U7-STATUS-Pad10)") (class "Default")
      (node (ref "U7") (pin "10") (pinfunction "STATUS_10") (pintype "bidirectional"))
    )
  )
)
